# MCU_V4.net
KiCad netlist of a schematic drawn in EAGLE
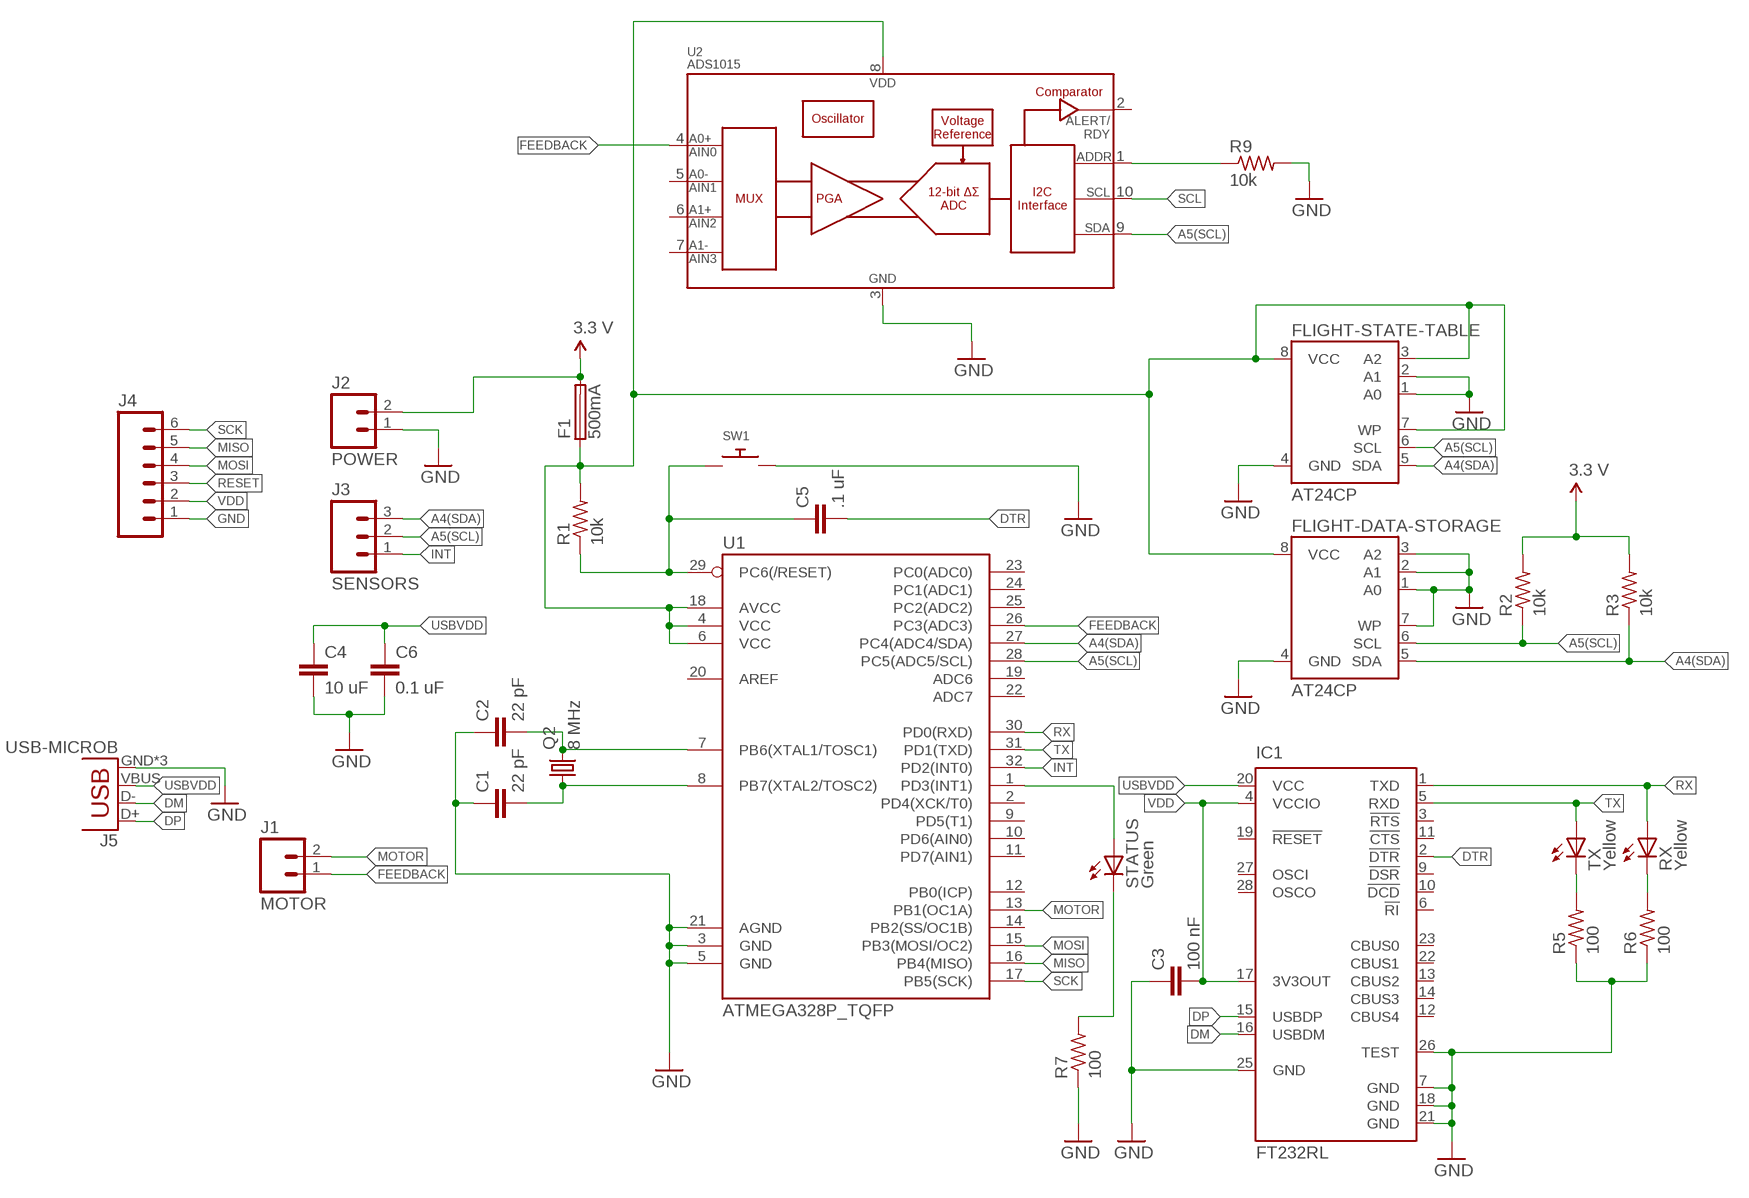
[diagram p0: schematic, sheet 1]

(export (version "E")
  (design (tool "Eeschema 10.0.6"))
  (components
    (comp (ref "C1")
      (value "22 pF")
      (footprint "eagle-import:C1206")
      (libsource (lib "eagle-import") (part "CC1206"))
    )
    (comp (ref "C2")
      (value "22 pF")
      (footprint "eagle-import:C1206")
      (libsource (lib "eagle-import") (part "CC1206"))
    )
    (comp (ref "C3")
      (value "100 nF")
      (footprint "eagle-import:C1206")
      (libsource (lib "eagle-import") (part "CC1206"))
    )
    (comp (ref "C4")
      (value "10 uF")
      (footprint "eagle-import:C1206")
      (libsource (lib "eagle-import") (part "CC1206"))
    )
    (comp (ref "C5")
      (value ".1 uF")
      (footprint "eagle-import:C1206")
      (libsource (lib "eagle-import") (part "CC1206"))
    )
    (comp (ref "C6")
      (value "0.1 uF")
      (footprint "eagle-import:C1206")
      (libsource (lib "eagle-import") (part "CC1206"))
    )
    (comp (ref "F1")
      (value "500mA")
      (footprint "eagle-import:PICOFUSE")
      (libsource (lib "eagle-import") (part "PICOFUSE"))
    )
    (comp (ref "FLIGHT-DATA-STORAGE")
      (value "AT24CP")
      (footprint "eagle-import:DIL08")
      (fields (field (name "MPN") "AT24C1024BW-SH-B"))
      (libsource (lib "eagle-import") (part "AT24CP"))
    )
    (comp (ref "FLIGHT-STATE-TABLE")
      (value "AT24CP")
      (footprint "eagle-import:DIL08")
      (fields (field (name "MPN") "AT24C1024BW-SH-B"))
      (libsource (lib "eagle-import") (part "AT24CP"))
    )
    (comp (ref "IC1")
      (value "FT232RL")
      (footprint "eagle-import:SSOP28")
      (libsource (lib "eagle-import") (part "FT232RL"))
    )
    (comp (ref "J1")
      (value "MOTOR")
      (footprint "eagle-import:1X02_LOCK")
      (libsource (lib "eagle-import") (part "M02LOCK"))
    )
    (comp (ref "J2")
      (value "POWER")
      (footprint "eagle-import:1X02_LOCK")
      (libsource (lib "eagle-import") (part "M02LOCK"))
    )
    (comp (ref "J3")
      (value "SENSORS")
      (footprint "eagle-import:1X03_LOCK")
      (libsource (lib "eagle-import") (part "M03LOCK"))
    )
    (comp (ref "J4")
      (value "M06LOCK")
      (footprint "eagle-import:1X06_LOCK")
      (libsource (lib "eagle-import") (part "M06LOCK"))
    )
    (comp (ref "J5")
      (value "USB-MICROB")
      (footprint "eagle-import:USB-MICROB")
      (libsource (lib "eagle-import") (part "USB-MICROB"))
    )
    (comp (ref "Q2")
      (value "8 MHz")
      (footprint "eagle-import:HC49_S")
      (libsource (lib "eagle-import") (part "CRYSTALHC49S"))
    )
    (comp (ref "R1")
      (value "10k")
      (footprint "eagle-import:R1206")
      (libsource (lib "eagle-import") (part "R-US_R1206"))
    )
    (comp (ref "R2")
      (value "10k")
      (footprint "eagle-import:R1206")
      (libsource (lib "eagle-import") (part "R-US_R1206"))
    )
    (comp (ref "R3")
      (value "10k")
      (footprint "eagle-import:R1206")
      (libsource (lib "eagle-import") (part "R-US_R1206"))
    )
    (comp (ref "R5")
      (value "100")
      (footprint "eagle-import:R1206")
      (libsource (lib "eagle-import") (part "R-US_R1206"))
    )
    (comp (ref "R6")
      (value "100")
      (footprint "eagle-import:R1206")
      (libsource (lib "eagle-import") (part "R-US_R1206"))
    )
    (comp (ref "R7")
      (value "100")
      (footprint "eagle-import:R1206")
      (libsource (lib "eagle-import") (part "R-US_R1206"))
    )
    (comp (ref "R9")
      (value "10k")
      (footprint "eagle-import:R1206")
      (libsource (lib "eagle-import") (part "R-US_R1206"))
    )
    (comp (ref "RX")
      (value "Yellow")
      (footprint "eagle-import:CHIPLED_1206")
      (libsource (lib "eagle-import") (part "LEDCHIPLED_1206"))
    )
    (comp (ref "STATUS")
      (value "Green")
      (footprint "eagle-import:CHIPLED_1206")
      (libsource (lib "eagle-import") (part "LEDCHIPLED_1206"))
    )
    (comp (ref "SW1")
      (value "SWITCH_PUSHBUTTONSOFTTOUCHSMD_SJ")
      (footprint "eagle-import:PUSHBUTTON_SMD_SJ")
      (libsource (lib "eagle-import") (part "SWITCH_PUSHBUTTONSOFTTOUCHSMD_SJ"))
    )
    (comp (ref "TX")
      (value "Yellow")
      (footprint "eagle-import:CHIPLED_1206")
      (libsource (lib "eagle-import") (part "LEDCHIPLED_1206"))
    )
    (comp (ref "U1")
      (value "ATMEGA328P_TQFP")
      (footprint "eagle-import:TQFP32-08")
      (libsource (lib "eagle-import") (part "ATMEGA328P_TQFP"))
    )
    (comp (ref "U2")
      (value "ADS1015")
      (footprint "eagle-import:MSOP10")
      (libsource (lib "eagle-import") (part "ADS1015"))
    )
  )
  (nets
    (net (code "1") (name "A4(SDA)") (class "Default")
      (node (ref "FLIGHT-DATA-STORAGE") (pin "5") (pinfunction "SDA_5") (pintype "bidirectional"))
      (node (ref "FLIGHT-STATE-TABLE") (pin "5") (pinfunction "SDA_5") (pintype "bidirectional"))
      (node (ref "J3") (pin "3") (pinfunction "3_3") (pintype "passive"))
      (node (ref "R3") (pin "1") (pinfunction "1_1") (pintype "passive"))
      (node (ref "R9") (pin "1") (pinfunction "1_1") (pintype "passive"))
      (node (ref "U1") (pin "27") (pinfunction "PC4(ADC4/SDA)_27") (pintype "bidirectional"))
      (node (ref "U2") (pin "1") (pinfunction "ADDR_1") (pintype "bidirectional"))
    )
    (net (code "2") (name "A5(SCL)") (class "Default")
      (node (ref "FLIGHT-DATA-STORAGE") (pin "6") (pinfunction "SCL_6") (pintype "bidirectional"))
      (node (ref "FLIGHT-STATE-TABLE") (pin "6") (pinfunction "SCL_6") (pintype "bidirectional"))
      (node (ref "J3") (pin "2") (pinfunction "2_2") (pintype "passive"))
      (node (ref "R2") (pin "1") (pinfunction "1_1") (pintype "passive"))
      (node (ref "U1") (pin "28") (pinfunction "PC5(ADC5/SCL)_28") (pintype "bidirectional"))
      (node (ref "U2") (pin "9") (pinfunction "SDA_9") (pintype "bidirectional"))
    )
    (net (code "3") (name "DM") (class "Default")
      (node (ref "IC1") (pin "16") (pinfunction "USBDM_16") (pintype "bidirectional"))
      (node (ref "J5") (pin "D-") (pinfunction "D-_D-") (pintype "bidirectional"))
    )
    (net (code "4") (name "DP") (class "Default")
      (node (ref "IC1") (pin "15") (pinfunction "USBDP_15") (pintype "bidirectional"))
      (node (ref "J5") (pin "D+") (pinfunction "D+_D+") (pintype "bidirectional"))
    )
    (net (code "5") (name "DTR") (class "Default")
      (node (ref "C5") (pin "2") (pinfunction "2_2") (pintype "passive"))
      (node (ref "IC1") (pin "2") (pinfunction "~{DTR}_2") (pintype "output"))
    )
    (net (code "6") (name "FEEDBACK") (class "Default")
      (node (ref "J1") (pin "1") (pinfunction "1_1") (pintype "passive"))
      (node (ref "U1") (pin "26") (pinfunction "PC3(ADC3)_26") (pintype "bidirectional"))
      (node (ref "U2") (pin "4") (pinfunction "AIN0_4") (pintype "bidirectional"))
    )
    (net (code "7") (name "GND") (class "Default")
      (node (ref "C1") (pin "1") (pinfunction "1_1") (pintype "passive"))
      (node (ref "C2") (pin "1") (pinfunction "1_1") (pintype "passive"))
      (node (ref "C3") (pin "1") (pinfunction "1_1") (pintype "passive"))
      (node (ref "C4") (pin "2") (pinfunction "2_2") (pintype "passive"))
      (node (ref "C6") (pin "2") (pinfunction "2_2") (pintype "passive"))
      (node (ref "FLIGHT-DATA-STORAGE") (pin "1") (pinfunction "A0_1") (pintype "input"))
      (node (ref "FLIGHT-DATA-STORAGE") (pin "2") (pinfunction "A1_2") (pintype "input"))
      (node (ref "FLIGHT-DATA-STORAGE") (pin "3") (pinfunction "A2_3") (pintype "input"))
      (node (ref "FLIGHT-DATA-STORAGE") (pin "4") (pinfunction "GND_4") (pintype "power_in"))
      (node (ref "FLIGHT-DATA-STORAGE") (pin "7") (pinfunction "WP_7") (pintype "input"))
      (node (ref "FLIGHT-STATE-TABLE") (pin "1") (pinfunction "A0_1") (pintype "input"))
      (node (ref "FLIGHT-STATE-TABLE") (pin "2") (pinfunction "A1_2") (pintype "input"))
      (node (ref "FLIGHT-STATE-TABLE") (pin "4") (pinfunction "GND_4") (pintype "power_in"))
      (node (ref "IC1") (pin "18") (pinfunction "GND_18") (pintype "power_in"))
      (node (ref "IC1") (pin "21") (pinfunction "GND_21") (pintype "power_in"))
      (node (ref "IC1") (pin "25") (pinfunction "GND_25") (pintype "power_in"))
      (node (ref "IC1") (pin "26") (pinfunction "TEST_26") (pintype "input"))
      (node (ref "IC1") (pin "7") (pinfunction "GND_7") (pintype "power_in"))
      (node (ref "J2") (pin "1") (pinfunction "1_1") (pintype "passive"))
      (node (ref "J4") (pin "1") (pinfunction "1_1") (pintype "passive"))
      (node (ref "J5") (pin "GND") (pinfunction "GND_GND") (pintype "bidirectional"))
      (node (ref "J5") (pin "MT1") (pinfunction "GND_MT1") (pintype "bidirectional"))
      (node (ref "J5") (pin "MT2") (pinfunction "GND_MT2") (pintype "bidirectional"))
      (node (ref "R5") (pin "1") (pinfunction "1_1") (pintype "passive"))
      (node (ref "R6") (pin "1") (pinfunction "1_1") (pintype "passive"))
      (node (ref "R7") (pin "1") (pinfunction "1_1") (pintype "passive"))
      (node (ref "R9") (pin "2") (pinfunction "2_2") (pintype "passive"))
      (node (ref "SW1") (pin "P$2") (pinfunction "P$2_P$2") (pintype "passive"))
      (node (ref "U1") (pin "21") (pinfunction "AGND_21") (pintype "bidirectional"))
      (node (ref "U1") (pin "3") (pinfunction "GND_3") (pintype "bidirectional"))
      (node (ref "U1") (pin "5") (pinfunction "GND_5") (pintype "bidirectional"))
      (node (ref "U2") (pin "3") (pinfunction "VSS_3") (pintype "bidirectional"))
    )
    (net (code "8") (name "INT") (class "Default")
      (node (ref "J3") (pin "1") (pinfunction "1_1") (pintype "passive"))
      (node (ref "U1") (pin "32") (pinfunction "PD2(INT0)_32") (pintype "bidirectional"))
    )
    (net (code "9") (name "MISO") (class "Default")
      (node (ref "J4") (pin "5") (pinfunction "5_5") (pintype "passive"))
      (node (ref "U1") (pin "16") (pinfunction "PB4(MISO)_16") (pintype "bidirectional"))
    )
    (net (code "10") (name "MOSI") (class "Default")
      (node (ref "J4") (pin "4") (pinfunction "4_4") (pintype "passive"))
      (node (ref "U1") (pin "15") (pinfunction "PB3(MOSI/OC2)_15") (pintype "bidirectional"))
    )
    (net (code "11") (name "MOTOR") (class "Default")
      (node (ref "J1") (pin "2") (pinfunction "2_2") (pintype "passive"))
      (node (ref "U1") (pin "13") (pinfunction "PB1(OC1A)_13") (pintype "bidirectional"))
    )
    (net (code "12") (name "Net-(FLIGHT-DATA-STORAGE-VCC)") (class "Default")
      (node (ref "F1") (pin "1") (pinfunction "1_1") (pintype "passive"))
      (node (ref "FLIGHT-DATA-STORAGE") (pin "8") (pinfunction "VCC_8") (pintype "power_in"))
      (node (ref "FLIGHT-STATE-TABLE") (pin "3") (pinfunction "A2_3") (pintype "input"))
      (node (ref "FLIGHT-STATE-TABLE") (pin "7") (pinfunction "WP_7") (pintype "input"))
      (node (ref "FLIGHT-STATE-TABLE") (pin "8") (pinfunction "VCC_8") (pintype "power_in"))
      (node (ref "R1") (pin "2") (pinfunction "2_2") (pintype "passive"))
      (node (ref "U1") (pin "18") (pinfunction "AVCC_18") (pintype "bidirectional"))
      (node (ref "U1") (pin "4") (pinfunction "VCC_4") (pintype "bidirectional"))
      (node (ref "U1") (pin "6") (pinfunction "VCC_6") (pintype "bidirectional"))
      (node (ref "U2") (pin "8") (pinfunction "VDD_8") (pintype "bidirectional"))
    )
    (net (code "13") (name "Net-(R5-Pad2)") (class "Default")
      (node (ref "R5") (pin "2") (pinfunction "2_2") (pintype "passive"))
      (node (ref "TX") (pin "C") (pinfunction "C_C") (pintype "passive"))
    )
    (net (code "14") (name "Net-(R6-Pad2)") (class "Default")
      (node (ref "R6") (pin "2") (pinfunction "2_2") (pintype "passive"))
      (node (ref "RX") (pin "C") (pinfunction "C_C") (pintype "passive"))
    )
    (net (code "15") (name "Net-(R7-Pad2)") (class "Default")
      (node (ref "R7") (pin "2") (pinfunction "2_2") (pintype "passive"))
      (node (ref "STATUS") (pin "C") (pinfunction "C_C") (pintype "passive"))
    )
    (net (code "16") (name "Net-(U1-PB6(XTAL1{slash}TOSC1))") (class "Default")
      (node (ref "C2") (pin "2") (pinfunction "2_2") (pintype "passive"))
      (node (ref "Q2") (pin "2") (pinfunction "2_2") (pintype "passive"))
      (node (ref "U1") (pin "7") (pinfunction "PB6(XTAL1/TOSC1)_7") (pintype "bidirectional"))
    )
    (net (code "17") (name "Net-(U1-PB7(XTAL2{slash}TOSC2))") (class "Default")
      (node (ref "C1") (pin "2") (pinfunction "2_2") (pintype "passive"))
      (node (ref "Q2") (pin "1") (pinfunction "1_1") (pintype "passive"))
      (node (ref "U1") (pin "8") (pinfunction "PB7(XTAL2/TOSC2)_8") (pintype "bidirectional"))
    )
    (net (code "18") (name "Net-(U1-PD3(INT1))") (class "Default")
      (node (ref "STATUS") (pin "A") (pinfunction "A_A") (pintype "passive"))
      (node (ref "U1") (pin "1") (pinfunction "PD3(INT1)_1") (pintype "bidirectional"))
    )
    (net (code "19") (name "RESET") (class "Default")
      (node (ref "C5") (pin "1") (pinfunction "1_1") (pintype "passive"))
      (node (ref "J4") (pin "3") (pinfunction "3_3") (pintype "passive"))
      (node (ref "R1") (pin "1") (pinfunction "1_1") (pintype "passive"))
      (node (ref "SW1") (pin "P$1") (pinfunction "P$1_P$1") (pintype "passive"))
      (node (ref "U1") (pin "29") (pinfunction "PC6(/RESET)_29") (pintype "bidirectional"))
    )
    (net (code "20") (name "RX") (class "Default")
      (node (ref "IC1") (pin "1") (pinfunction "TXD_1") (pintype "output"))
      (node (ref "RX") (pin "A") (pinfunction "A_A") (pintype "passive"))
      (node (ref "U1") (pin "30") (pinfunction "PD0(RXD)_30") (pintype "bidirectional"))
    )
    (net (code "21") (name "SCK") (class "Default")
      (node (ref "J4") (pin "6") (pinfunction "6_6") (pintype "passive"))
      (node (ref "U1") (pin "17") (pinfunction "PB5(SCK)_17") (pintype "bidirectional"))
    )
    (net (code "22") (name "SCL") (class "Default")
      (node (ref "U2") (pin "10") (pinfunction "SCL_10") (pintype "bidirectional"))
    )
    (net (code "23") (name "TX") (class "Default")
      (node (ref "IC1") (pin "5") (pinfunction "RXD_5") (pintype "input"))
      (node (ref "TX") (pin "A") (pinfunction "A_A") (pintype "passive"))
      (node (ref "U1") (pin "31") (pinfunction "PD1(TXD)_31") (pintype "bidirectional"))
    )
    (net (code "24") (name "USBVDD") (class "Default")
      (node (ref "C4") (pin "1") (pinfunction "1_1") (pintype "passive"))
      (node (ref "C6") (pin "1") (pinfunction "1_1") (pintype "passive"))
      (node (ref "IC1") (pin "20") (pinfunction "VCC_20") (pintype "power_in"))
      (node (ref "J5") (pin "VBUS") (pinfunction "VBUS_VBUS") (pintype "bidirectional"))
    )
    (net (code "25") (name "VDD") (class "Default")
      (node (ref "C3") (pin "2") (pinfunction "2_2") (pintype "passive"))
      (node (ref "F1") (pin "2") (pinfunction "2_2") (pintype "passive"))
      (node (ref "IC1") (pin "17") (pinfunction "3V3OUT_17") (pintype "output"))
      (node (ref "IC1") (pin "4") (pinfunction "VCCIO_4") (pintype "power_in"))
      (node (ref "J2") (pin "2") (pinfunction "2_2") (pintype "passive"))
      (node (ref "J4") (pin "2") (pinfunction "2_2") (pintype "passive"))
      (node (ref "R2") (pin "2") (pinfunction "2_2") (pintype "passive"))
      (node (ref "R3") (pin "2") (pinfunction "2_2") (pintype "passive"))
    )
    (net (code "26") (name "unconnected-(IC1-CBUS0-Pad23)") (class "Default")
      (node (ref "IC1") (pin "23") (pinfunction "CBUS0_23") (pintype "bidirectional"))
    )
    (net (code "27") (name "unconnected-(IC1-CBUS1-Pad22)") (class "Default")
      (node (ref "IC1") (pin "22") (pinfunction "CBUS1_22") (pintype "bidirectional"))
    )
    (net (code "28") (name "unconnected-(IC1-CBUS2-Pad13)") (class "Default")
      (node (ref "IC1") (pin "13") (pinfunction "CBUS2_13") (pintype "bidirectional"))
    )
    (net (code "29") (name "unconnected-(IC1-CBUS3-Pad14)") (class "Default")
      (node (ref "IC1") (pin "14") (pinfunction "CBUS3_14") (pintype "bidirectional"))
    )
    (net (code "30") (name "unconnected-(IC1-CBUS4-Pad12)") (class "Default")
      (node (ref "IC1") (pin "12") (pinfunction "CBUS4_12") (pintype "bidirectional"))
    )
    (net (code "31") (name "unconnected-(IC1-OSCI-Pad27)") (class "Default")
      (node (ref "IC1") (pin "27") (pinfunction "OSCI_27") (pintype "input"))
    )
    (net (code "32") (name "unconnected-(IC1-OSCO-Pad28)") (class "Default")
      (node (ref "IC1") (pin "28") (pinfunction "OSCO_28") (pintype "output"))
    )
    (net (code "33") (name "unconnected-(IC1-~{CTS}-Pad11)") (class "Default")
      (node (ref "IC1") (pin "11") (pinfunction "~{CTS}_11") (pintype "input"))
    )
    (net (code "34") (name "unconnected-(IC1-~{DCD}-Pad10)") (class "Default")
      (node (ref "IC1") (pin "10") (pinfunction "~{DCD}_10") (pintype "input"))
    )
    (net (code "35") (name "unconnected-(IC1-~{DSR}-Pad9)") (class "Default")
      (node (ref "IC1") (pin "9") (pinfunction "~{DSR}_9") (pintype "input"))
    )
    (net (code "36") (name "unconnected-(IC1-~{RESET}-Pad19)") (class "Default")
      (node (ref "IC1") (pin "19") (pinfunction "~{RESET}_19") (pintype "input"))
    )
    (net (code "37") (name "unconnected-(IC1-~{RI}-Pad6)") (class "Default")
      (node (ref "IC1") (pin "6") (pinfunction "~{RI}_6") (pintype "input"))
    )
    (net (code "38") (name "unconnected-(IC1-~{RTS}-Pad3)") (class "Default")
      (node (ref "IC1") (pin "3") (pinfunction "~{RTS}_3") (pintype "output"))
    )
    (net (code "39") (name "unconnected-(U1-ADC6-Pad19)") (class "Default")
      (node (ref "U1") (pin "19") (pinfunction "ADC6_19") (pintype "bidirectional"))
    )
    (net (code "40") (name "unconnected-(U1-ADC7-Pad22)") (class "Default")
      (node (ref "U1") (pin "22") (pinfunction "ADC7_22") (pintype "bidirectional"))
    )
    (net (code "41") (name "unconnected-(U1-AREF-Pad20)") (class "Default")
      (node (ref "U1") (pin "20") (pinfunction "AREF_20") (pintype "bidirectional"))
    )
    (net (code "42") (name "unconnected-(U1-PB0(ICP)-Pad12)") (class "Default")
      (node (ref "U1") (pin "12") (pinfunction "PB0(ICP)_12") (pintype "bidirectional"))
    )
    (net (code "43") (name "unconnected-(U1-PB2(SS{slash}OC1B)-Pad14)") (class "Default")
      (node (ref "U1") (pin "14") (pinfunction "PB2(SS/OC1B)_14") (pintype "bidirectional"))
    )
    (net (code "44") (name "unconnected-(U1-PC0(ADC0)-Pad23)") (class "Default")
      (node (ref "U1") (pin "23") (pinfunction "PC0(ADC0)_23") (pintype "bidirectional"))
    )
    (net (code "45") (name "unconnected-(U1-PC1(ADC1)-Pad24)") (class "Default")
      (node (ref "U1") (pin "24") (pinfunction "PC1(ADC1)_24") (pintype "bidirectional"))
    )
    (net (code "46") (name "unconnected-(U1-PC2(ADC2)-Pad25)") (class "Default")
      (node (ref "U1") (pin "25") (pinfunction "PC2(ADC2)_25") (pintype "bidirectional"))
    )
    (net (code "47") (name "unconnected-(U1-PD4(XCK{slash}T0)-Pad2)") (class "Default")
      (node (ref "U1") (pin "2") (pinfunction "PD4(XCK/T0)_2") (pintype "bidirectional"))
    )
    (net (code "48") (name "unconnected-(U1-PD5(T1)-Pad9)") (class "Default")
      (node (ref "U1") (pin "9") (pinfunction "PD5(T1)_9") (pintype "bidirectional"))
    )
    (net (code "49") (name "unconnected-(U1-PD6(AIN0)-Pad10)") (class "Default")
      (node (ref "U1") (pin "10") (pinfunction "PD6(AIN0)_10") (pintype "bidirectional"))
    )
    (net (code "50") (name "unconnected-(U1-PD7(AIN1)-Pad11)") (class "Default")
      (node (ref "U1") (pin "11") (pinfunction "PD7(AIN1)_11") (pintype "bidirectional"))
    )
    (net (code "51") (name "unconnected-(U2-AIN1-Pad5)") (class "Default")
      (node (ref "U2") (pin "5") (pinfunction "AIN1_5") (pintype "bidirectional"))
    )
    (net (code "52") (name "unconnected-(U2-AIN2-Pad6)") (class "Default")
      (node (ref "U2") (pin "6") (pinfunction "AIN2_6") (pintype "bidirectional"))
    )
    (net (code "53") (name "unconnected-(U2-AIN3-Pad7)") (class "Default")
      (node (ref "U2") (pin "7") (pinfunction "AIN3_7") (pintype "bidirectional"))
    )
    (net (code "54") (name "unconnected-(U2-ALERT{slash}RDY-Pad2)") (class "Default")
      (node (ref "U2") (pin "2") (pinfunction "ALERT/RDY_2") (pintype "bidirectional"))
    )
  )
)
